# MotorEncoder.net
KiCad netlist of a schematic drawn in EAGLE
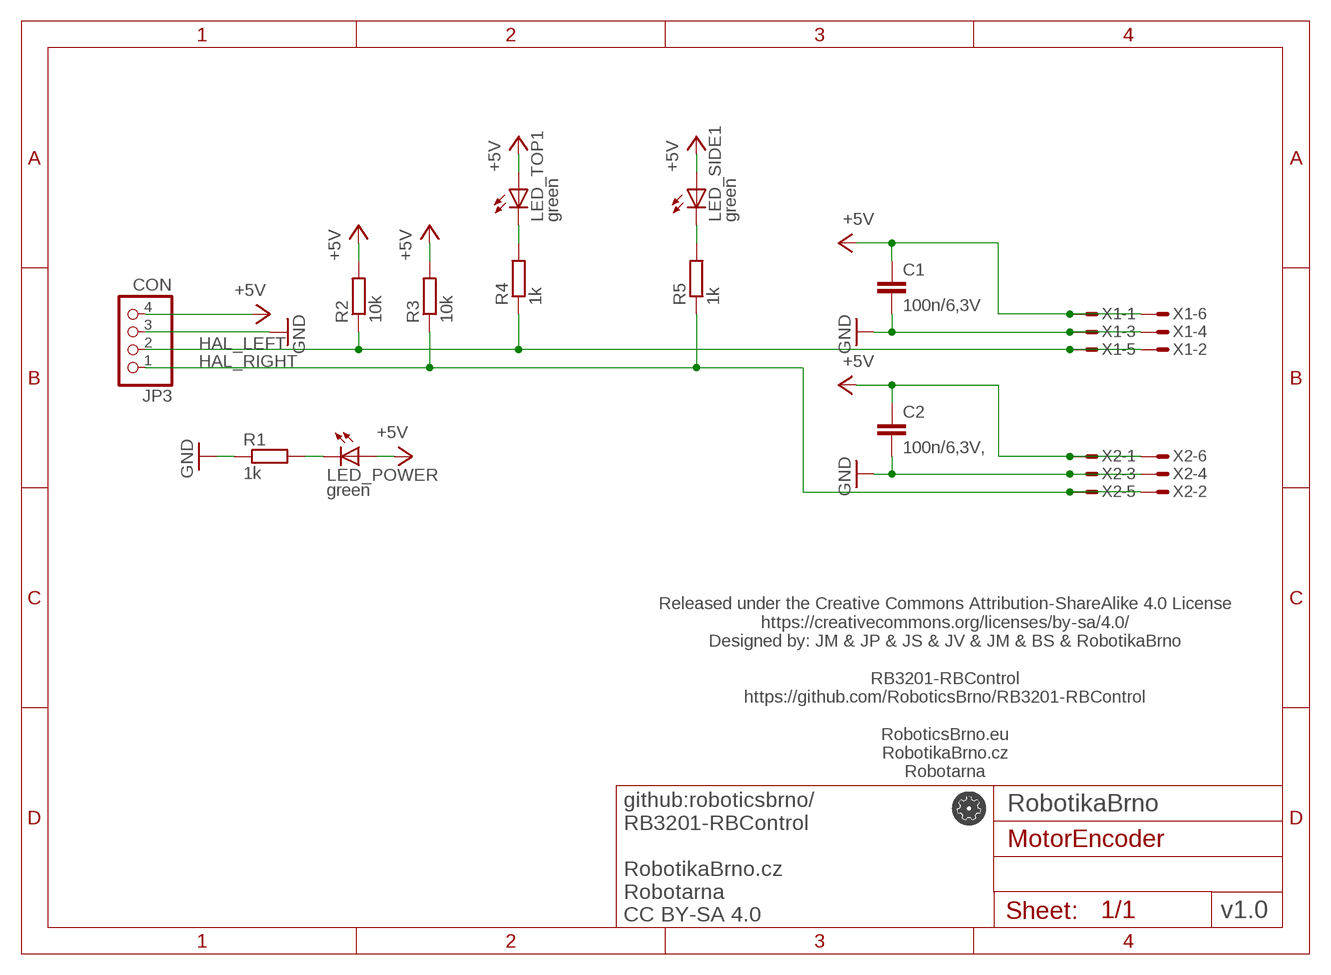
[diagram p0: schematic, sheet 1]

(export (version "E")
  (design (tool "Eeschema 10.0.6"))
  (components
    (comp (ref "C1")
      (value "100n/6,3V")
      (footprint "eagle-import:C0603")
      (libsource (lib "eagle-import") (part "C-EUC0603"))
    )
    (comp (ref "C2")
      (value "100n/6,3V,")
      (footprint "eagle-import:C0603")
      (libsource (lib "eagle-import") (part "C-EUC0603"))
    )
    (comp (ref "JP3")
      (value "CON")
      (footprint "eagle-import:1X04_90")
      (libsource (lib "eagle-import") (part "PINHD-1X4/90"))
    )
    (comp (ref "LED_POWER")
      (value "green")
      (footprint "eagle-import:CHIPLED_0603")
      (libsource (lib "eagle-import") (part "LEDCHIPLED_0603"))
    )
    (comp (ref "LED_SIDE1")
      (value "green")
      (footprint "eagle-import:CHIPLED_0603")
      (libsource (lib "eagle-import") (part "LEDCHIPLED_0603"))
    )
    (comp (ref "LED_TOP1")
      (value "green")
      (footprint "eagle-import:CHIPLED_0603")
      (libsource (lib "eagle-import") (part "LEDCHIPLED_0603"))
    )
    (comp (ref "R1")
      (value "1k")
      (footprint "eagle-import:R0603")
      (libsource (lib "eagle-import") (part "R-EU_R0603"))
    )
    (comp (ref "R2")
      (value "10k")
      (footprint "eagle-import:R0603")
      (libsource (lib "eagle-import") (part "R-EU_R0603"))
    )
    (comp (ref "R3")
      (value "10k")
      (footprint "eagle-import:R0603")
      (libsource (lib "eagle-import") (part "R-EU_R0603"))
    )
    (comp (ref "R4")
      (value "1k")
      (footprint "eagle-import:R0603")
      (libsource (lib "eagle-import") (part "R-EU_R0603"))
    )
    (comp (ref "R5")
      (value "1k")
      (footprint "eagle-import:R0603")
      (libsource (lib "eagle-import") (part "R-EU_R0603"))
    )
    (comp (ref "X1")
      (value "PHB_1MM27_2X03_SNT_S")
      (footprint "eagle-import:PHB_1MM27_2X03_SNT")
      (libsource (lib "eagle-import") (part "PHB_1MM27_2X03_?_SSNT"))
    )
    (comp (ref "X2")
      (value "PHB_1MM27_2X03_SNT_S")
      (footprint "eagle-import:PHB_1MM27_2X03_SNT")
      (libsource (lib "eagle-import") (part "PHB_1MM27_2X03_?_SSNT"))
    )
  )
  (nets
    (net (code "1") (name "+5V") (class "Default")
      (node (ref "C1") (pin "1") (pinfunction "1_1") (pintype "passive"))
      (node (ref "C2") (pin "1") (pinfunction "1_1") (pintype "passive"))
      (node (ref "JP3") (pin "4") (pinfunction "4_4") (pintype "passive"))
      (node (ref "LED_POWER") (pin "A") (pinfunction "A_A") (pintype "passive"))
      (node (ref "LED_SIDE1") (pin "A") (pinfunction "A_A") (pintype "passive"))
      (node (ref "LED_TOP1") (pin "A") (pinfunction "A_A") (pintype "passive"))
      (node (ref "R2") (pin "2") (pinfunction "2_2") (pintype "passive"))
      (node (ref "R3") (pin "2") (pinfunction "2_2") (pintype "passive"))
      (node (ref "X1") (pin "1") (pinfunction "S_1") (pintype "passive"))
      (node (ref "X1") (pin "6") (pinfunction "S_6") (pintype "passive"))
      (node (ref "X2") (pin "1") (pinfunction "S_1") (pintype "passive"))
      (node (ref "X2") (pin "6") (pinfunction "S_6") (pintype "passive"))
    )
    (net (code "2") (name "/HAL_LEFT") (class "Default")
      (node (ref "JP3") (pin "2") (pinfunction "2_2") (pintype "passive"))
      (node (ref "R2") (pin "1") (pinfunction "1_1") (pintype "passive"))
      (node (ref "R4") (pin "1") (pinfunction "1_1") (pintype "passive"))
      (node (ref "X1") (pin "2") (pinfunction "S_2") (pintype "passive"))
      (node (ref "X1") (pin "5") (pinfunction "S_5") (pintype "passive"))
    )
    (net (code "3") (name "/HAL_RIGHT") (class "Default")
      (node (ref "JP3") (pin "1") (pinfunction "1_1") (pintype "passive"))
      (node (ref "R3") (pin "1") (pinfunction "1_1") (pintype "passive"))
      (node (ref "R5") (pin "1") (pinfunction "1_1") (pintype "passive"))
      (node (ref "X2") (pin "2") (pinfunction "S_2") (pintype "passive"))
      (node (ref "X2") (pin "5") (pinfunction "S_5") (pintype "passive"))
    )
    (net (code "4") (name "GND") (class "Default")
      (node (ref "C1") (pin "2") (pinfunction "2_2") (pintype "passive"))
      (node (ref "C2") (pin "2") (pinfunction "2_2") (pintype "passive"))
      (node (ref "JP3") (pin "3") (pinfunction "3_3") (pintype "passive"))
      (node (ref "R1") (pin "1") (pinfunction "1_1") (pintype "passive"))
      (node (ref "X1") (pin "3") (pinfunction "S_3") (pintype "passive"))
      (node (ref "X1") (pin "4") (pinfunction "S_4") (pintype "passive"))
      (node (ref "X2") (pin "3") (pinfunction "S_3") (pintype "passive"))
      (node (ref "X2") (pin "4") (pinfunction "S_4") (pintype "passive"))
    )
    (net (code "5") (name "Net-(LED_POWER-PadC)") (class "Default")
      (node (ref "LED_POWER") (pin "C") (pinfunction "C_C") (pintype "passive"))
      (node (ref "R1") (pin "2") (pinfunction "2_2") (pintype "passive"))
    )
    (net (code "6") (name "Net-(LED_SIDE1-PadC)") (class "Default")
      (node (ref "LED_SIDE1") (pin "C") (pinfunction "C_C") (pintype "passive"))
      (node (ref "R5") (pin "2") (pinfunction "2_2") (pintype "passive"))
    )
    (net (code "7") (name "Net-(LED_TOP1-PadC)") (class "Default")
      (node (ref "LED_TOP1") (pin "C") (pinfunction "C_C") (pintype "passive"))
      (node (ref "R4") (pin "2") (pinfunction "2_2") (pintype "passive"))
    )
  )
)
